# button_debounce_pos.net
KiCad netlist of a schematic drawn in EAGLE
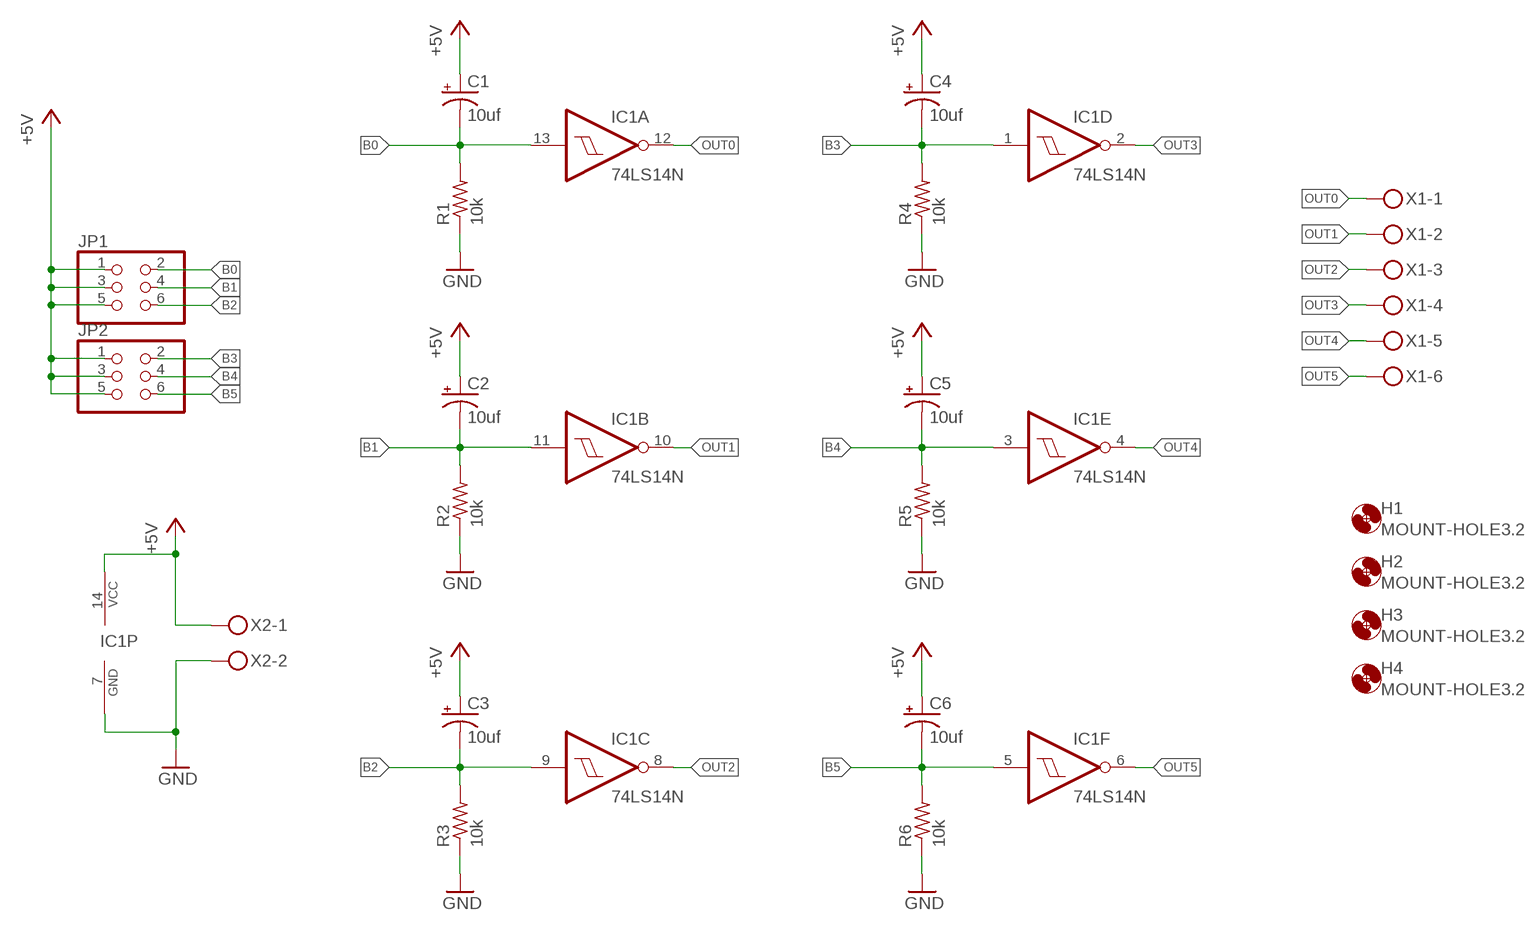
[diagram p0: schematic, sheet 1]

(export (version "E")
  (design (tool "Eeschema 10.0.6"))
  (components
    (comp (ref "C1")
      (value "10uf")
      (footprint "eagle-import:E2-5")
      (libsource (lib "eagle-import") (part "CPOL-USE2-5"))
    )
    (comp (ref "C2")
      (value "10uf")
      (footprint "eagle-import:E2-5")
      (libsource (lib "eagle-import") (part "CPOL-USE2-5"))
    )
    (comp (ref "C3")
      (value "10uf")
      (footprint "eagle-import:E2-5")
      (libsource (lib "eagle-import") (part "CPOL-USE2-5"))
    )
    (comp (ref "C4")
      (value "10uf")
      (footprint "eagle-import:E2-5")
      (libsource (lib "eagle-import") (part "CPOL-USE2-5"))
    )
    (comp (ref "C5")
      (value "10uf")
      (footprint "eagle-import:E2-5")
      (libsource (lib "eagle-import") (part "CPOL-USE2-5"))
    )
    (comp (ref "C6")
      (value "10uf")
      (footprint "eagle-import:E2-5")
      (libsource (lib "eagle-import") (part "CPOL-USE2-5"))
    )
    (comp (ref "H1")
      (value "MOUNT-HOLE3.2")
      (footprint "eagle-import:3,2")
      (libsource (lib "eagle-import") (part "MOUNT-HOLE3.2"))
    )
    (comp (ref "H2")
      (value "MOUNT-HOLE3.2")
      (footprint "eagle-import:3,2")
      (libsource (lib "eagle-import") (part "MOUNT-HOLE3.2"))
    )
    (comp (ref "H3")
      (value "MOUNT-HOLE3.2")
      (footprint "eagle-import:3,2")
      (libsource (lib "eagle-import") (part "MOUNT-HOLE3.2"))
    )
    (comp (ref "H4")
      (value "MOUNT-HOLE3.2")
      (footprint "eagle-import:3,2")
      (libsource (lib "eagle-import") (part "MOUNT-HOLE3.2"))
    )
    (comp (ref "IC1")
      (value "74LS14N")
      (footprint "eagle-import:DIL14")
      (libsource (lib "eagle-import") (part "7414NLS"))
    )
    (comp (ref "JP1")
      (value "PINHD-2X3")
      (footprint "eagle-import:2X03")
      (libsource (lib "eagle-import") (part "PINHD-2X3"))
    )
    (comp (ref "JP2")
      (value "PINHD-2X3")
      (footprint "eagle-import:2X03")
      (libsource (lib "eagle-import") (part "PINHD-2X3"))
    )
    (comp (ref "R1")
      (value "10k")
      (footprint "eagle-import:0207_2V")
      (libsource (lib "eagle-import") (part "R-US_0207/2V"))
    )
    (comp (ref "R2")
      (value "10k")
      (footprint "eagle-import:0207_2V")
      (libsource (lib "eagle-import") (part "R-US_0207/2V"))
    )
    (comp (ref "R3")
      (value "10k")
      (footprint "eagle-import:0207_2V")
      (libsource (lib "eagle-import") (part "R-US_0207/2V"))
    )
    (comp (ref "R4")
      (value "10k")
      (footprint "eagle-import:0207_2V")
      (libsource (lib "eagle-import") (part "R-US_0207/2V"))
    )
    (comp (ref "R5")
      (value "10k")
      (footprint "eagle-import:0207_2V")
      (libsource (lib "eagle-import") (part "R-US_0207/2V"))
    )
    (comp (ref "R6")
      (value "10k")
      (footprint "eagle-import:0207_2V")
      (libsource (lib "eagle-import") (part "R-US_0207/2V"))
    )
    (comp (ref "X1")
      (value "MKDSN1,5/6-5,08")
      (footprint "eagle-import:MKDSN1,5_6-5,08")
      (libsource (lib "eagle-import") (part "MKDSN1,5/6-5,08"))
    )
    (comp (ref "X2")
      (value "MKDSN1,5/2-5,08")
      (footprint "eagle-import:MKDSN1,5_2-5,08")
      (libsource (lib "eagle-import") (part "MKDSN1,5/2-5,08"))
    )
  )
  (nets
    (net (code "1") (name "+5V") (class "Default")
      (node (ref "C1") (pin "+") (pinfunction "+_+") (pintype "passive"))
      (node (ref "C2") (pin "+") (pinfunction "+_+") (pintype "passive"))
      (node (ref "C3") (pin "+") (pinfunction "+_+") (pintype "passive"))
      (node (ref "C4") (pin "+") (pinfunction "+_+") (pintype "passive"))
      (node (ref "C5") (pin "+") (pinfunction "+_+") (pintype "passive"))
      (node (ref "C6") (pin "+") (pinfunction "+_+") (pintype "passive"))
      (node (ref "IC1") (pin "14") (pinfunction "VCC_14") (pintype "power_in"))
      (node (ref "JP1") (pin "1") (pinfunction "1_1") (pintype "passive"))
      (node (ref "JP1") (pin "3") (pinfunction "3_3") (pintype "passive"))
      (node (ref "JP1") (pin "5") (pinfunction "5_5") (pintype "passive"))
      (node (ref "JP2") (pin "1") (pinfunction "1_1") (pintype "passive"))
      (node (ref "JP2") (pin "3") (pinfunction "3_3") (pintype "passive"))
      (node (ref "JP2") (pin "5") (pinfunction "5_5") (pintype "passive"))
      (node (ref "X2") (pin "1") (pinfunction "KL_1") (pintype "passive"))
    )
    (net (code "2") (name "B0") (class "Default")
      (node (ref "C1") (pin "-") (pinfunction "-_-") (pintype "passive"))
      (node (ref "IC1") (pin "13") (pinfunction "I_13") (pintype "input"))
      (node (ref "JP1") (pin "2") (pinfunction "2_2") (pintype "passive"))
      (node (ref "R1") (pin "2") (pinfunction "2_2") (pintype "passive"))
    )
    (net (code "3") (name "B1") (class "Default")
      (node (ref "C2") (pin "-") (pinfunction "-_-") (pintype "passive"))
      (node (ref "IC1") (pin "11") (pinfunction "I_11") (pintype "input"))
      (node (ref "JP1") (pin "4") (pinfunction "4_4") (pintype "passive"))
      (node (ref "R2") (pin "2") (pinfunction "2_2") (pintype "passive"))
    )
    (net (code "4") (name "B2") (class "Default")
      (node (ref "C3") (pin "-") (pinfunction "-_-") (pintype "passive"))
      (node (ref "IC1") (pin "9") (pinfunction "I_9") (pintype "input"))
      (node (ref "JP1") (pin "6") (pinfunction "6_6") (pintype "passive"))
      (node (ref "R3") (pin "2") (pinfunction "2_2") (pintype "passive"))
    )
    (net (code "5") (name "B3") (class "Default")
      (node (ref "C4") (pin "-") (pinfunction "-_-") (pintype "passive"))
      (node (ref "IC1") (pin "1") (pinfunction "I_1") (pintype "input"))
      (node (ref "JP2") (pin "2") (pinfunction "2_2") (pintype "passive"))
      (node (ref "R4") (pin "2") (pinfunction "2_2") (pintype "passive"))
    )
    (net (code "6") (name "B4") (class "Default")
      (node (ref "C5") (pin "-") (pinfunction "-_-") (pintype "passive"))
      (node (ref "IC1") (pin "3") (pinfunction "I_3") (pintype "input"))
      (node (ref "JP2") (pin "4") (pinfunction "4_4") (pintype "passive"))
      (node (ref "R5") (pin "2") (pinfunction "2_2") (pintype "passive"))
    )
    (net (code "7") (name "B5") (class "Default")
      (node (ref "C6") (pin "-") (pinfunction "-_-") (pintype "passive"))
      (node (ref "IC1") (pin "5") (pinfunction "I_5") (pintype "input"))
      (node (ref "JP2") (pin "6") (pinfunction "6_6") (pintype "passive"))
      (node (ref "R6") (pin "2") (pinfunction "2_2") (pintype "passive"))
    )
    (net (code "8") (name "GND") (class "Default")
      (node (ref "IC1") (pin "7") (pinfunction "GND_7") (pintype "power_in"))
      (node (ref "R1") (pin "1") (pinfunction "1_1") (pintype "passive"))
      (node (ref "R2") (pin "1") (pinfunction "1_1") (pintype "passive"))
      (node (ref "R3") (pin "1") (pinfunction "1_1") (pintype "passive"))
      (node (ref "R4") (pin "1") (pinfunction "1_1") (pintype "passive"))
      (node (ref "R5") (pin "1") (pinfunction "1_1") (pintype "passive"))
      (node (ref "R6") (pin "1") (pinfunction "1_1") (pintype "passive"))
      (node (ref "X2") (pin "2") (pinfunction "KL_2") (pintype "passive"))
    )
    (net (code "9") (name "OUT0") (class "Default")
      (node (ref "IC1") (pin "12") (pinfunction "O_12") (pintype "output"))
      (node (ref "X1") (pin "1") (pinfunction "KL_1") (pintype "passive"))
    )
    (net (code "10") (name "OUT1") (class "Default")
      (node (ref "IC1") (pin "10") (pinfunction "O_10") (pintype "output"))
      (node (ref "X1") (pin "2") (pinfunction "KL_2") (pintype "passive"))
    )
    (net (code "11") (name "OUT2") (class "Default")
      (node (ref "IC1") (pin "8") (pinfunction "O_8") (pintype "output"))
      (node (ref "X1") (pin "3") (pinfunction "KL_3") (pintype "passive"))
    )
    (net (code "12") (name "OUT3") (class "Default")
      (node (ref "IC1") (pin "2") (pinfunction "O_2") (pintype "output"))
      (node (ref "X1") (pin "4") (pinfunction "KL_4") (pintype "passive"))
    )
    (net (code "13") (name "OUT4") (class "Default")
      (node (ref "IC1") (pin "4") (pinfunction "O_4") (pintype "output"))
      (node (ref "X1") (pin "5") (pinfunction "KL_5") (pintype "passive"))
    )
    (net (code "14") (name "OUT5") (class "Default")
      (node (ref "IC1") (pin "6") (pinfunction "O_6") (pintype "output"))
      (node (ref "X1") (pin "6") (pinfunction "KL_6") (pintype "passive"))
    )
  )
)
